# con68k-switch.net
KiCad netlist of a schematic drawn in EAGLE
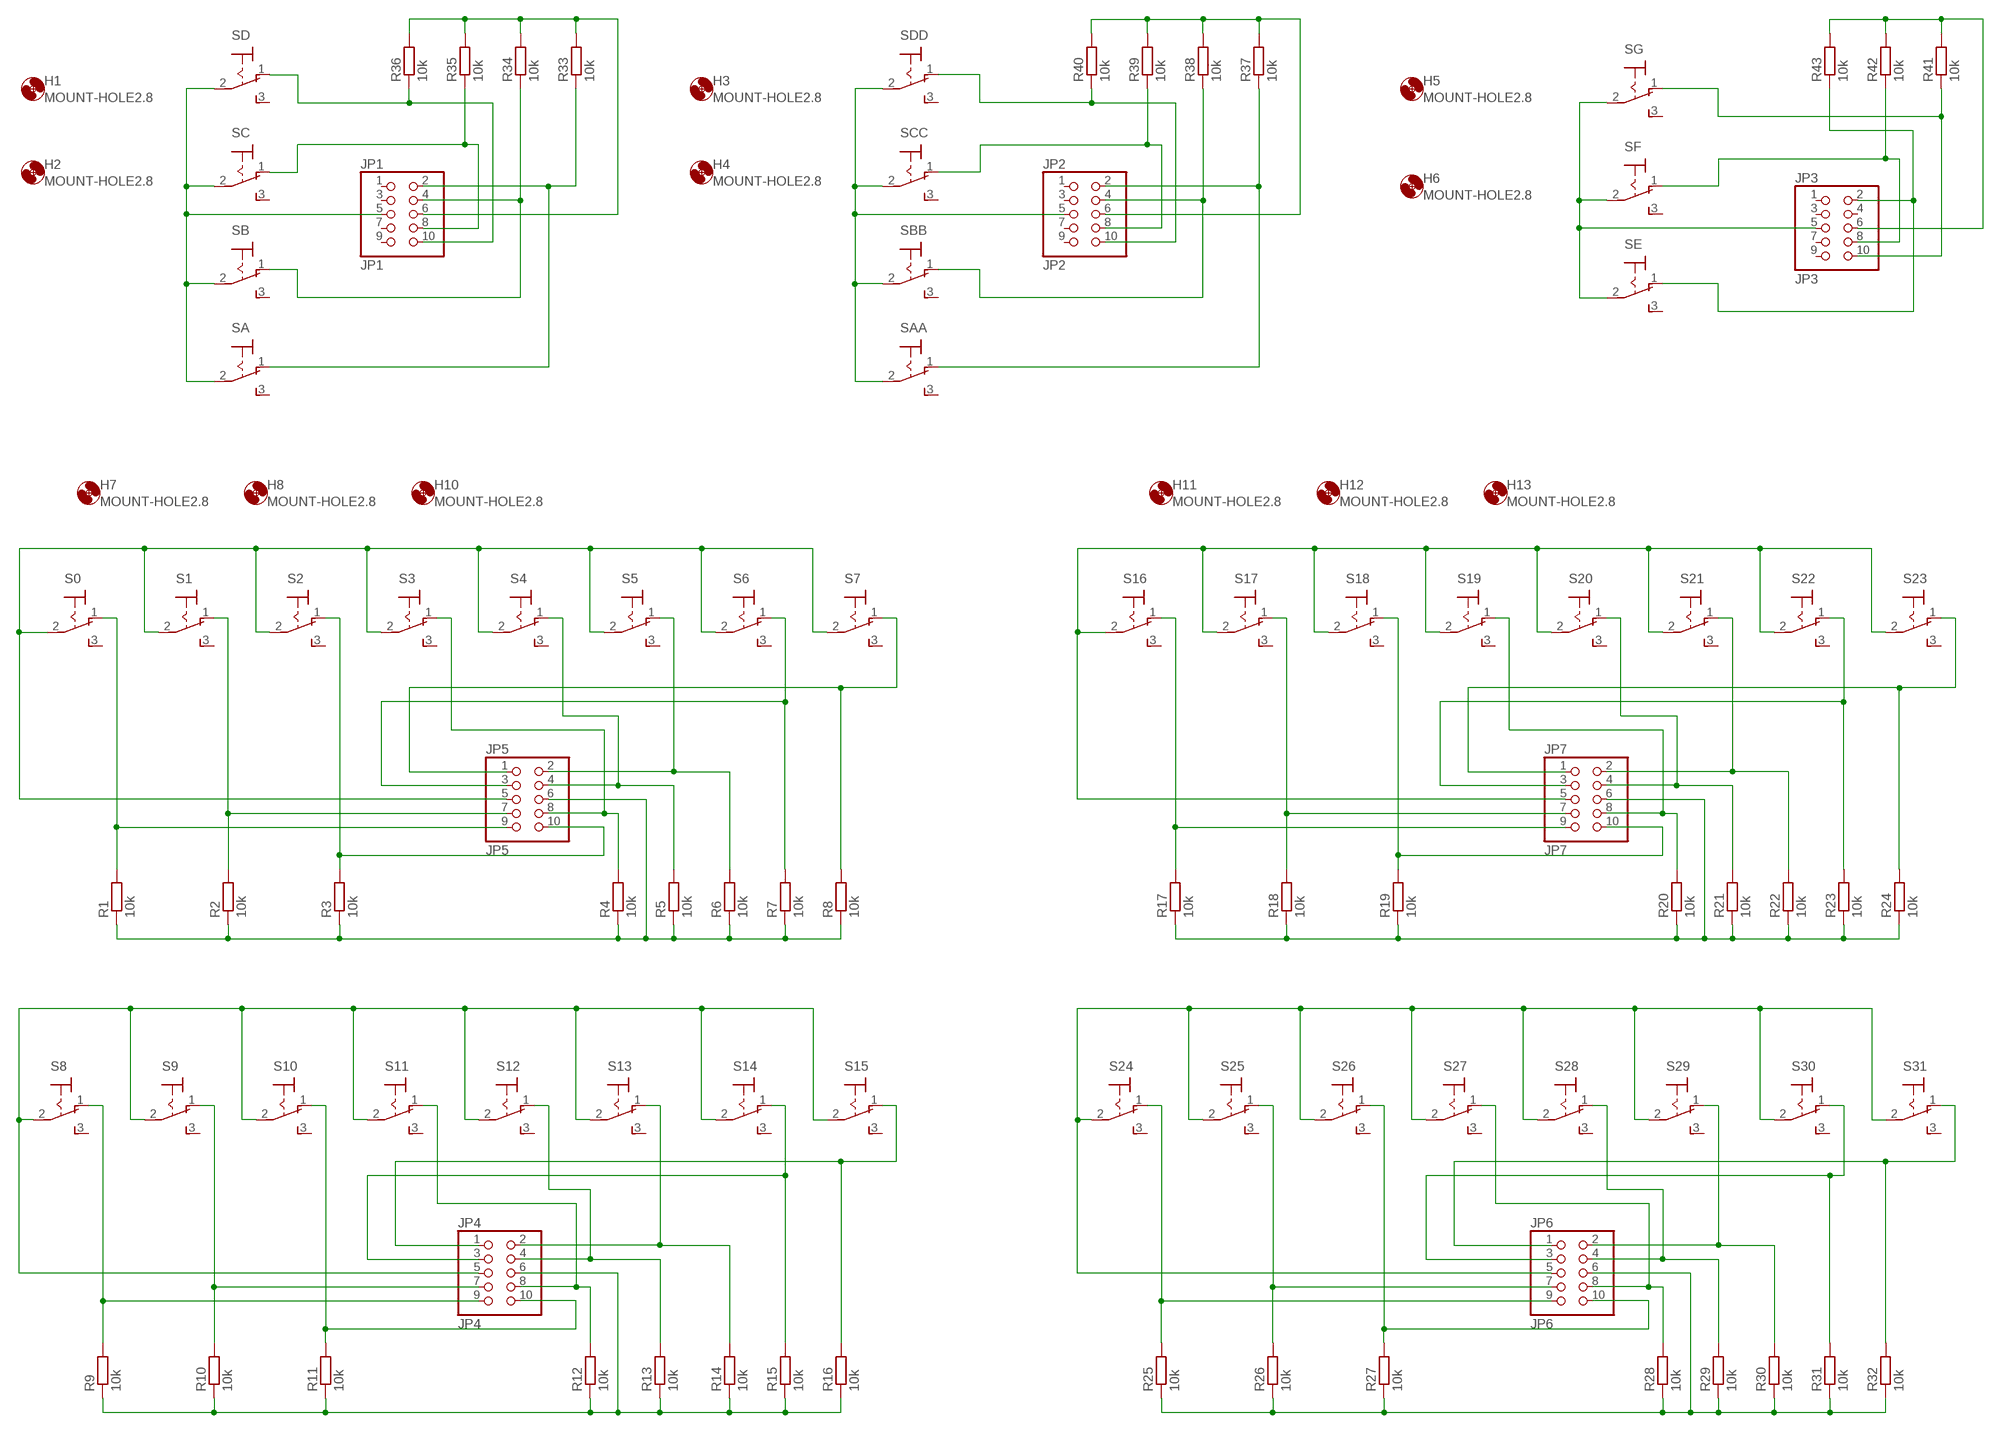
[diagram p0: schematic, sheet 1]

(export (version "E")
  (design (tool "Eeschema 10.0.6"))
  (components
    (comp (ref "H1")
      (value "MOUNT-HOLE2.8")
      (footprint "eagle-import:2,8")
      (libsource (lib "eagle-import") (part "MOUNT-HOLE2.8"))
    )
    (comp (ref "H2")
      (value "MOUNT-HOLE2.8")
      (footprint "eagle-import:2,8")
      (libsource (lib "eagle-import") (part "MOUNT-HOLE2.8"))
    )
    (comp (ref "H3")
      (value "MOUNT-HOLE2.8")
      (footprint "eagle-import:2,8")
      (libsource (lib "eagle-import") (part "MOUNT-HOLE2.8"))
    )
    (comp (ref "H4")
      (value "MOUNT-HOLE2.8")
      (footprint "eagle-import:2,8")
      (libsource (lib "eagle-import") (part "MOUNT-HOLE2.8"))
    )
    (comp (ref "H5")
      (value "MOUNT-HOLE2.8")
      (footprint "eagle-import:2,8")
      (libsource (lib "eagle-import") (part "MOUNT-HOLE2.8"))
    )
    (comp (ref "H6")
      (value "MOUNT-HOLE2.8")
      (footprint "eagle-import:2,8")
      (libsource (lib "eagle-import") (part "MOUNT-HOLE2.8"))
    )
    (comp (ref "H7")
      (value "MOUNT-HOLE2.8")
      (footprint "eagle-import:2,8")
      (libsource (lib "eagle-import") (part "MOUNT-HOLE2.8"))
    )
    (comp (ref "H8")
      (value "MOUNT-HOLE2.8")
      (footprint "eagle-import:2,8")
      (libsource (lib "eagle-import") (part "MOUNT-HOLE2.8"))
    )
    (comp (ref "H10")
      (value "MOUNT-HOLE2.8")
      (footprint "eagle-import:2,8")
      (libsource (lib "eagle-import") (part "MOUNT-HOLE2.8"))
    )
    (comp (ref "H11")
      (value "MOUNT-HOLE2.8")
      (footprint "eagle-import:2,8")
      (libsource (lib "eagle-import") (part "MOUNT-HOLE2.8"))
    )
    (comp (ref "H12")
      (value "MOUNT-HOLE2.8")
      (footprint "eagle-import:2,8")
      (libsource (lib "eagle-import") (part "MOUNT-HOLE2.8"))
    )
    (comp (ref "H13")
      (value "MOUNT-HOLE2.8")
      (footprint "eagle-import:2,8")
      (libsource (lib "eagle-import") (part "MOUNT-HOLE2.8"))
    )
    (comp (ref "JP1")
      (value "JP1")
      (footprint "eagle-import:2X05")
      (libsource (lib "eagle-import") (part "PINHD-2X5"))
    )
    (comp (ref "JP2")
      (value "JP2")
      (footprint "eagle-import:2X05")
      (libsource (lib "eagle-import") (part "PINHD-2X5"))
    )
    (comp (ref "JP3")
      (value "JP3")
      (footprint "eagle-import:2X05")
      (libsource (lib "eagle-import") (part "PINHD-2X5"))
    )
    (comp (ref "JP4")
      (value "JP4")
      (footprint "eagle-import:2X05")
      (libsource (lib "eagle-import") (part "PINHD-2X5"))
    )
    (comp (ref "JP5")
      (value "JP5")
      (footprint "eagle-import:2X05")
      (libsource (lib "eagle-import") (part "PINHD-2X5"))
    )
    (comp (ref "JP6")
      (value "JP6")
      (footprint "eagle-import:2X05")
      (libsource (lib "eagle-import") (part "PINHD-2X5"))
    )
    (comp (ref "JP7")
      (value "JP7")
      (footprint "eagle-import:2X05")
      (libsource (lib "eagle-import") (part "PINHD-2X5"))
    )
    (comp (ref "R1")
      (value "10k")
      (footprint "eagle-import:0204_7")
      (libsource (lib "eagle-import") (part "R-EU_0204/7"))
    )
    (comp (ref "R2")
      (value "10k")
      (footprint "eagle-import:0204_7")
      (libsource (lib "eagle-import") (part "R-EU_0204/7"))
    )
    (comp (ref "R3")
      (value "10k")
      (footprint "eagle-import:0204_7")
      (libsource (lib "eagle-import") (part "R-EU_0204/7"))
    )
    (comp (ref "R4")
      (value "10k")
      (footprint "eagle-import:0204_7")
      (libsource (lib "eagle-import") (part "R-EU_0204/7"))
    )
    (comp (ref "R5")
      (value "10k")
      (footprint "eagle-import:0204_7")
      (libsource (lib "eagle-import") (part "R-EU_0204/7"))
    )
    (comp (ref "R6")
      (value "10k")
      (footprint "eagle-import:0204_7")
      (libsource (lib "eagle-import") (part "R-EU_0204/7"))
    )
    (comp (ref "R7")
      (value "10k")
      (footprint "eagle-import:0204_7")
      (libsource (lib "eagle-import") (part "R-EU_0204/7"))
    )
    (comp (ref "R8")
      (value "10k")
      (footprint "eagle-import:0204_7")
      (libsource (lib "eagle-import") (part "R-EU_0204/7"))
    )
    (comp (ref "R9")
      (value "10k")
      (footprint "eagle-import:0204_7")
      (libsource (lib "eagle-import") (part "R-EU_0204/7"))
    )
    (comp (ref "R10")
      (value "10k")
      (footprint "eagle-import:0204_7")
      (libsource (lib "eagle-import") (part "R-EU_0204/7"))
    )
    (comp (ref "R11")
      (value "10k")
      (footprint "eagle-import:0204_7")
      (libsource (lib "eagle-import") (part "R-EU_0204/7"))
    )
    (comp (ref "R12")
      (value "10k")
      (footprint "eagle-import:0204_7")
      (libsource (lib "eagle-import") (part "R-EU_0204/7"))
    )
    (comp (ref "R13")
      (value "10k")
      (footprint "eagle-import:0204_7")
      (libsource (lib "eagle-import") (part "R-EU_0204/7"))
    )
    (comp (ref "R14")
      (value "10k")
      (footprint "eagle-import:0204_7")
      (libsource (lib "eagle-import") (part "R-EU_0204/7"))
    )
    (comp (ref "R15")
      (value "10k")
      (footprint "eagle-import:0204_7")
      (libsource (lib "eagle-import") (part "R-EU_0204/7"))
    )
    (comp (ref "R16")
      (value "10k")
      (footprint "eagle-import:0204_7")
      (libsource (lib "eagle-import") (part "R-EU_0204/7"))
    )
    (comp (ref "R17")
      (value "10k")
      (footprint "eagle-import:0204_7")
      (libsource (lib "eagle-import") (part "R-EU_0204/7"))
    )
    (comp (ref "R18")
      (value "10k")
      (footprint "eagle-import:0204_7")
      (libsource (lib "eagle-import") (part "R-EU_0204/7"))
    )
    (comp (ref "R19")
      (value "10k")
      (footprint "eagle-import:0204_7")
      (libsource (lib "eagle-import") (part "R-EU_0204/7"))
    )
    (comp (ref "R20")
      (value "10k")
      (footprint "eagle-import:0204_7")
      (libsource (lib "eagle-import") (part "R-EU_0204/7"))
    )
    (comp (ref "R21")
      (value "10k")
      (footprint "eagle-import:0204_7")
      (libsource (lib "eagle-import") (part "R-EU_0204/7"))
    )
    (comp (ref "R22")
      (value "10k")
      (footprint "eagle-import:0204_7")
      (libsource (lib "eagle-import") (part "R-EU_0204/7"))
    )
    (comp (ref "R23")
      (value "10k")
      (footprint "eagle-import:0204_7")
      (libsource (lib "eagle-import") (part "R-EU_0204/7"))
    )
    (comp (ref "R24")
      (value "10k")
      (footprint "eagle-import:0204_7")
      (libsource (lib "eagle-import") (part "R-EU_0204/7"))
    )
    (comp (ref "R25")
      (value "10k")
      (footprint "eagle-import:0204_7")
      (libsource (lib "eagle-import") (part "R-EU_0204/7"))
    )
    (comp (ref "R26")
      (value "10k")
      (footprint "eagle-import:0204_7")
      (libsource (lib "eagle-import") (part "R-EU_0204/7"))
    )
    (comp (ref "R27")
      (value "10k")
      (footprint "eagle-import:0204_7")
      (libsource (lib "eagle-import") (part "R-EU_0204/7"))
    )
    (comp (ref "R28")
      (value "10k")
      (footprint "eagle-import:0204_7")
      (libsource (lib "eagle-import") (part "R-EU_0204/7"))
    )
    (comp (ref "R29")
      (value "10k")
      (footprint "eagle-import:0204_7")
      (libsource (lib "eagle-import") (part "R-EU_0204/7"))
    )
    (comp (ref "R30")
      (value "10k")
      (footprint "eagle-import:0204_7")
      (libsource (lib "eagle-import") (part "R-EU_0204/7"))
    )
    (comp (ref "R31")
      (value "10k")
      (footprint "eagle-import:0204_7")
      (libsource (lib "eagle-import") (part "R-EU_0204/7"))
    )
    (comp (ref "R32")
      (value "10k")
      (footprint "eagle-import:0204_7")
      (libsource (lib "eagle-import") (part "R-EU_0204/7"))
    )
    (comp (ref "R33")
      (value "10k")
      (footprint "eagle-import:0204_7")
      (libsource (lib "eagle-import") (part "R-EU_0204/7"))
    )
    (comp (ref "R34")
      (value "10k")
      (footprint "eagle-import:0204_7")
      (libsource (lib "eagle-import") (part "R-EU_0204/7"))
    )
    (comp (ref "R35")
      (value "10k")
      (footprint "eagle-import:0204_7")
      (libsource (lib "eagle-import") (part "R-EU_0204/7"))
    )
    (comp (ref "R36")
      (value "10k")
      (footprint "eagle-import:0204_7")
      (libsource (lib "eagle-import") (part "R-EU_0204/7"))
    )
    (comp (ref "R37")
      (value "10k")
      (footprint "eagle-import:0204_7")
      (libsource (lib "eagle-import") (part "R-EU_0204/7"))
    )
    (comp (ref "R38")
      (value "10k")
      (footprint "eagle-import:0204_7")
      (libsource (lib "eagle-import") (part "R-EU_0204/7"))
    )
    (comp (ref "R39")
      (value "10k")
      (footprint "eagle-import:0204_7")
      (libsource (lib "eagle-import") (part "R-EU_0204/7"))
    )
    (comp (ref "R40")
      (value "10k")
      (footprint "eagle-import:0204_7")
      (libsource (lib "eagle-import") (part "R-EU_0204/7"))
    )
    (comp (ref "R41")
      (value "10k")
      (footprint "eagle-import:0204_7")
      (libsource (lib "eagle-import") (part "R-EU_0204/7"))
    )
    (comp (ref "R42")
      (value "10k")
      (footprint "eagle-import:0204_7")
      (libsource (lib "eagle-import") (part "R-EU_0204/7"))
    )
    (comp (ref "R43")
      (value "10k")
      (footprint "eagle-import:0204_7")
      (libsource (lib "eagle-import") (part "R-EU_0204/7"))
    )
    (comp (ref "S0")
      (value "M9040P")
      (footprint "eagle-import:M9040P")
      (libsource (lib "eagle-import") (part "M9040P"))
    )
    (comp (ref "S1")
      (value "M9040P")
      (footprint "eagle-import:M9040P")
      (libsource (lib "eagle-import") (part "M9040P"))
    )
    (comp (ref "S2")
      (value "M9040P")
      (footprint "eagle-import:M9040P")
      (libsource (lib "eagle-import") (part "M9040P"))
    )
    (comp (ref "S3")
      (value "M9040P")
      (footprint "eagle-import:M9040P")
      (libsource (lib "eagle-import") (part "M9040P"))
    )
    (comp (ref "S4")
      (value "M9040P")
      (footprint "eagle-import:M9040P")
      (libsource (lib "eagle-import") (part "M9040P"))
    )
    (comp (ref "S5")
      (value "M9040P")
      (footprint "eagle-import:M9040P")
      (libsource (lib "eagle-import") (part "M9040P"))
    )
    (comp (ref "S6")
      (value "M9040P")
      (footprint "eagle-import:M9040P")
      (libsource (lib "eagle-import") (part "M9040P"))
    )
    (comp (ref "S7")
      (value "M9040P")
      (footprint "eagle-import:M9040P")
      (libsource (lib "eagle-import") (part "M9040P"))
    )
    (comp (ref "S8")
      (value "M9040P")
      (footprint "eagle-import:M9040P")
      (libsource (lib "eagle-import") (part "M9040P"))
    )
    (comp (ref "S9")
      (value "M9040P")
      (footprint "eagle-import:M9040P")
      (libsource (lib "eagle-import") (part "M9040P"))
    )
    (comp (ref "S10")
      (value "M9040P")
      (footprint "eagle-import:M9040P")
      (libsource (lib "eagle-import") (part "M9040P"))
    )
    (comp (ref "S11")
      (value "M9040P")
      (footprint "eagle-import:M9040P")
      (libsource (lib "eagle-import") (part "M9040P"))
    )
    (comp (ref "S12")
      (value "M9040P")
      (footprint "eagle-import:M9040P")
      (libsource (lib "eagle-import") (part "M9040P"))
    )
    (comp (ref "S13")
      (value "M9040P")
      (footprint "eagle-import:M9040P")
      (libsource (lib "eagle-import") (part "M9040P"))
    )
    (comp (ref "S14")
      (value "M9040P")
      (footprint "eagle-import:M9040P")
      (libsource (lib "eagle-import") (part "M9040P"))
    )
    (comp (ref "S15")
      (value "M9040P")
      (footprint "eagle-import:M9040P")
      (libsource (lib "eagle-import") (part "M9040P"))
    )
    (comp (ref "S16")
      (value "M9040P")
      (footprint "eagle-import:M9040P")
      (libsource (lib "eagle-import") (part "M9040P"))
    )
    (comp (ref "S17")
      (value "M9040P")
      (footprint "eagle-import:M9040P")
      (libsource (lib "eagle-import") (part "M9040P"))
    )
    (comp (ref "S18")
      (value "M9040P")
      (footprint "eagle-import:M9040P")
      (libsource (lib "eagle-import") (part "M9040P"))
    )
    (comp (ref "S19")
      (value "M9040P")
      (footprint "eagle-import:M9040P")
      (libsource (lib "eagle-import") (part "M9040P"))
    )
    (comp (ref "S20")
      (value "M9040P")
      (footprint "eagle-import:M9040P")
      (libsource (lib "eagle-import") (part "M9040P"))
    )
    (comp (ref "S21")
      (value "M9040P")
      (footprint "eagle-import:M9040P")
      (libsource (lib "eagle-import") (part "M9040P"))
    )
    (comp (ref "S22")
      (value "M9040P")
      (footprint "eagle-import:M9040P")
      (libsource (lib "eagle-import") (part "M9040P"))
    )
    (comp (ref "S23")
      (value "M9040P")
      (footprint "eagle-import:M9040P")
      (libsource (lib "eagle-import") (part "M9040P"))
    )
    (comp (ref "S24")
      (value "M9040P")
      (footprint "eagle-import:M9040P")
      (libsource (lib "eagle-import") (part "M9040P"))
    )
    (comp (ref "S25")
      (value "M9040P")
      (footprint "eagle-import:M9040P")
      (libsource (lib "eagle-import") (part "M9040P"))
    )
    (comp (ref "S26")
      (value "M9040P")
      (footprint "eagle-import:M9040P")
      (libsource (lib "eagle-import") (part "M9040P"))
    )
    (comp (ref "S27")
      (value "M9040P")
      (footprint "eagle-import:M9040P")
      (libsource (lib "eagle-import") (part "M9040P"))
    )
    (comp (ref "S28")
      (value "M9040P")
      (footprint "eagle-import:M9040P")
      (libsource (lib "eagle-import") (part "M9040P"))
    )
    (comp (ref "S29")
      (value "M9040P")
      (footprint "eagle-import:M9040P")
      (libsource (lib "eagle-import") (part "M9040P"))
    )
    (comp (ref "S30")
      (value "M9040P")
      (footprint "eagle-import:M9040P")
      (libsource (lib "eagle-import") (part "M9040P"))
    )
    (comp (ref "S31")
      (value "M9040P")
      (footprint "eagle-import:M9040P")
      (libsource (lib "eagle-import") (part "M9040P"))
    )
    (comp (ref "SA")
      (value "M9040P")
      (footprint "eagle-import:M9040P")
      (libsource (lib "eagle-import") (part "M9040P"))
    )
    (comp (ref "SAA")
      (value "M9040P")
      (footprint "eagle-import:M9040P")
      (libsource (lib "eagle-import") (part "M9040P"))
    )
    (comp (ref "SB")
      (value "M9040P")
      (footprint "eagle-import:M9040P")
      (libsource (lib "eagle-import") (part "M9040P"))
    )
    (comp (ref "SBB")
      (value "M9040P")
      (footprint "eagle-import:M9040P")
      (libsource (lib "eagle-import") (part "M9040P"))
    )
    (comp (ref "SC")
      (value "M9040P")
      (footprint "eagle-import:M9040P")
      (libsource (lib "eagle-import") (part "M9040P"))
    )
    (comp (ref "SCC")
      (value "M9040P")
      (footprint "eagle-import:M9040P")
      (libsource (lib "eagle-import") (part "M9040P"))
    )
    (comp (ref "SD")
      (value "M9040P")
      (footprint "eagle-import:M9040P")
      (libsource (lib "eagle-import") (part "M9040P"))
    )
    (comp (ref "SDD")
      (value "M9040P")
      (footprint "eagle-import:M9040P")
      (libsource (lib "eagle-import") (part "M9040P"))
    )
    (comp (ref "SE")
      (value "M9040P")
      (footprint "eagle-import:M9040P")
      (libsource (lib "eagle-import") (part "M9040P"))
    )
    (comp (ref "SF")
      (value "M9040P")
      (footprint "eagle-import:M9040P")
      (libsource (lib "eagle-import") (part "M9040P"))
    )
    (comp (ref "SG")
      (value "M9040P")
      (footprint "eagle-import:M9040P")
      (libsource (lib "eagle-import") (part "M9040P"))
    )
  )
  (nets
    (net (code "1") (name "Net-(JP1-Pad6)") (class "Default")
      (node (ref "JP1") (pin "6") (pinfunction "6_6") (pintype "passive"))
      (node (ref "R33") (pin "2") (pinfunction "2_2") (pintype "passive"))
      (node (ref "R34") (pin "2") (pinfunction "2_2") (pintype "passive"))
      (node (ref "R35") (pin "2") (pinfunction "2_2") (pintype "passive"))
      (node (ref "R36") (pin "2") (pinfunction "2_2") (pintype "passive"))
    )
    (net (code "2") (name "Net-(JP2-Pad6)") (class "Default")
      (node (ref "JP2") (pin "6") (pinfunction "6_6") (pintype "passive"))
      (node (ref "R37") (pin "2") (pinfunction "2_2") (pintype "passive"))
      (node (ref "R38") (pin "2") (pinfunction "2_2") (pintype "passive"))
      (node (ref "R39") (pin "2") (pinfunction "2_2") (pintype "passive"))
      (node (ref "R40") (pin "2") (pinfunction "2_2") (pintype "passive"))
    )
    (net (code "3") (name "Net-(JP3-Pad6)") (class "Default")
      (node (ref "JP3") (pin "6") (pinfunction "6_6") (pintype "passive"))
      (node (ref "R41") (pin "2") (pinfunction "2_2") (pintype "passive"))
      (node (ref "R42") (pin "2") (pinfunction "2_2") (pintype "passive"))
      (node (ref "R43") (pin "2") (pinfunction "2_2") (pintype "passive"))
    )
    (net (code "4") (name "Net-(JP4-Pad6)") (class "Default")
      (node (ref "JP4") (pin "6") (pinfunction "6_6") (pintype "passive"))
      (node (ref "R10") (pin "1") (pinfunction "1_1") (pintype "passive"))
      (node (ref "R11") (pin "1") (pinfunction "1_1") (pintype "passive"))
      (node (ref "R12") (pin "1") (pinfunction "1_1") (pintype "passive"))
      (node (ref "R13") (pin "1") (pinfunction "1_1") (pintype "passive"))
      (node (ref "R14") (pin "1") (pinfunction "1_1") (pintype "passive"))
      (node (ref "R15") (pin "1") (pinfunction "1_1") (pintype "passive"))
      (node (ref "R16") (pin "1") (pinfunction "1_1") (pintype "passive"))
      (node (ref "R9") (pin "1") (pinfunction "1_1") (pintype "passive"))
    )
    (net (code "5") (name "Net-(JP5-Pad6)") (class "Default")
      (node (ref "JP5") (pin "6") (pinfunction "6_6") (pintype "passive"))
      (node (ref "R1") (pin "1") (pinfunction "1_1") (pintype "passive"))
      (node (ref "R2") (pin "1") (pinfunction "1_1") (pintype "passive"))
      (node (ref "R3") (pin "1") (pinfunction "1_1") (pintype "passive"))
      (node (ref "R4") (pin "1") (pinfunction "1_1") (pintype "passive"))
      (node (ref "R5") (pin "1") (pinfunction "1_1") (pintype "passive"))
      (node (ref "R6") (pin "1") (pinfunction "1_1") (pintype "passive"))
      (node (ref "R7") (pin "1") (pinfunction "1_1") (pintype "passive"))
      (node (ref "R8") (pin "1") (pinfunction "1_1") (pintype "passive"))
    )
    (net (code "6") (name "Net-(JP6-Pad6)") (class "Default")
      (node (ref "JP6") (pin "6") (pinfunction "6_6") (pintype "passive"))
      (node (ref "R25") (pin "1") (pinfunction "1_1") (pintype "passive"))
      (node (ref "R26") (pin "1") (pinfunction "1_1") (pintype "passive"))
      (node (ref "R27") (pin "1") (pinfunction "1_1") (pintype "passive"))
      (node (ref "R28") (pin "1") (pinfunction "1_1") (pintype "passive"))
      (node (ref "R29") (pin "1") (pinfunction "1_1") (pintype "passive"))
      (node (ref "R30") (pin "1") (pinfunction "1_1") (pintype "passive"))
      (node (ref "R31") (pin "1") (pinfunction "1_1") (pintype "passive"))
      (node (ref "R32") (pin "1") (pinfunction "1_1") (pintype "passive"))
    )
    (net (code "7") (name "Net-(JP7-Pad6)") (class "Default")
      (node (ref "JP7") (pin "6") (pinfunction "6_6") (pintype "passive"))
      (node (ref "R17") (pin "1") (pinfunction "1_1") (pintype "passive"))
      (node (ref "R18") (pin "1") (pinfunction "1_1") (pintype "passive"))
      (node (ref "R19") (pin "1") (pinfunction "1_1") (pintype "passive"))
      (node (ref "R20") (pin "1") (pinfunction "1_1") (pintype "passive"))
      (node (ref "R21") (pin "1") (pinfunction "1_1") (pintype "passive"))
      (node (ref "R22") (pin "1") (pinfunction "1_1") (pintype "passive"))
      (node (ref "R23") (pin "1") (pinfunction "1_1") (pintype "passive"))
      (node (ref "R24") (pin "1") (pinfunction "1_1") (pintype "passive"))
    )
    (net (code "8") (name "Net-(S0-O)") (class "Default")
      (node (ref "JP5") (pin "9") (pinfunction "9_9") (pintype "passive"))
      (node (ref "R1") (pin "2") (pinfunction "2_2") (pintype "passive"))
      (node (ref "S0") (pin "1") (pinfunction "O_1") (pintype "passive"))
    )
    (net (code "9") (name "Net-(S0-P)") (class "Default")
      (node (ref "JP5") (pin "5") (pinfunction "5_5") (pintype "passive"))
      (node (ref "S0") (pin "2") (pinfunction "P_2") (pintype "passive"))
      (node (ref "S1") (pin "2") (pinfunction "P_2") (pintype "passive"))
      (node (ref "S2") (pin "2") (pinfunction "P_2") (pintype "passive"))
      (node (ref "S3") (pin "2") (pinfunction "P_2") (pintype "passive"))
      (node (ref "S4") (pin "2") (pinfunction "P_2") (pintype "passive"))
      (node (ref "S5") (pin "2") (pinfunction "P_2") (pintype "passive"))
      (node (ref "S6") (pin "2") (pinfunction "P_2") (pintype "passive"))
      (node (ref "S7") (pin "2") (pinfunction "P_2") (pintype "passive"))
    )
    (net (code "10") (name "Net-(S1-O)") (class "Default")
      (node (ref "JP5") (pin "7") (pinfunction "7_7") (pintype "passive"))
      (node (ref "R2") (pin "2") (pinfunction "2_2") (pintype "passive"))
      (node (ref "S1") (pin "1") (pinfunction "O_1") (pintype "passive"))
    )
    (net (code "11") (name "Net-(S2-O)") (class "Default")
      (node (ref "JP5") (pin "10") (pinfunction "10_10") (pintype "passive"))
      (node (ref "R3") (pin "2") (pinfunction "2_2") (pintype "passive"))
      (node (ref "S2") (pin "1") (pinfunction "O_1") (pintype "passive"))
    )
    (net (code "12") (name "Net-(S3-O)") (class "Default")
      (node (ref "JP5") (pin "8") (pinfunction "8_8") (pintype "passive"))
      (node (ref "R4") (pin "2") (pinfunction "2_2") (pintype "passive"))
      (node (ref "S3") (pin "1") (pinfunction "O_1") (pintype "passive"))
    )
    (net (code "13") (name "Net-(S4-O)") (class "Default")
      (node (ref "JP5") (pin "4") (pinfunction "4_4") (pintype "passive"))
      (node (ref "R5") (pin "2") (pinfunction "2_2") (pintype "passive"))
      (node (ref "S4") (pin "1") (pinfunction "O_1") (pintype "passive"))
    )
    (net (code "14") (name "Net-(S5-O)") (class "Default")
      (node (ref "JP5") (pin "2") (pinfunction "2_2") (pintype "passive"))
      (node (ref "R6") (pin "2") (pinfunction "2_2") (pintype "passive"))
      (node (ref "S5") (pin "1") (pinfunction "O_1") (pintype "passive"))
    )
    (net (code "15") (name "Net-(S6-O)") (class "Default")
      (node (ref "JP5") (pin "3") (pinfunction "3_3") (pintype "passive"))
      (node (ref "R7") (pin "2") (pinfunction "2_2") (pintype "passive"))
      (node (ref "S6") (pin "1") (pinfunction "O_1") (pintype "passive"))
    )
    (net (code "16") (name "Net-(S7-O)") (class "Default")
      (node (ref "JP5") (pin "1") (pinfunction "1_1") (pintype "passive"))
      (node (ref "R8") (pin "2") (pinfunction "2_2") (pintype "passive"))
      (node (ref "S7") (pin "1") (pinfunction "O_1") (pintype "passive"))
    )
    (net (code "17") (name "Net-(S8-O)") (class "Default")
      (node (ref "JP4") (pin "9") (pinfunction "9_9") (pintype "passive"))
      (node (ref "R9") (pin "2") (pinfunction "2_2") (pintype "passive"))
      (node (ref "S8") (pin "1") (pinfunction "O_1") (pintype "passive"))
    )
    (net (code "18") (name "Net-(S9-O)") (class "Default")
      (node (ref "JP4") (pin "7") (pinfunction "7_7") (pintype "passive"))
      (node (ref "R10") (pin "2") (pinfunction "2_2") (pintype "passive"))
      (node (ref "S9") (pin "1") (pinfunction "O_1") (pintype "passive"))
    )
    (net (code "19") (name "Net-(S10-O)") (class "Default")
      (node (ref "JP4") (pin "10") (pinfunction "10_10") (pintype "passive"))
      (node (ref "R11") (pin "2") (pinfunction "2_2") (pintype "passive"))
      (node (ref "S10") (pin "1") (pinfunction "O_1") (pintype "passive"))
    )
    (net (code "20") (name "Net-(S10-P)") (class "Default")
      (node (ref "JP4") (pin "5") (pinfunction "5_5") (pintype "passive"))
      (node (ref "S10") (pin "2") (pinfunction "P_2") (pintype "passive"))
      (node (ref "S11") (pin "2") (pinfunction "P_2") (pintype "passive"))
      (node (ref "S12") (pin "2") (pinfunction "P_2") (pintype "passive"))
      (node (ref "S13") (pin "2") (pinfunction "P_2") (pintype "passive"))
      (node (ref "S14") (pin "2") (pinfunction "P_2") (pintype "passive"))
      (node (ref "S15") (pin "2") (pinfunction "P_2") (pintype "passive"))
      (node (ref "S8") (pin "2") (pinfunction "P_2") (pintype "passive"))
      (node (ref "S9") (pin "2") (pinfunction "P_2") (pintype "passive"))
    )
    (net (code "21") (name "Net-(S11-O)") (class "Default")
      (node (ref "JP4") (pin "8") (pinfunction "8_8") (pintype "passive"))
      (node (ref "R12") (pin "2") (pinfunction "2_2") (pintype "passive"))
      (node (ref "S11") (pin "1") (pinfunction "O_1") (pintype "passive"))
    )
    (net (code "22") (name "Net-(S12-O)") (class "Default")
      (node (ref "JP4") (pin "4") (pinfunction "4_4") (pintype "passive"))
      (node (ref "R13") (pin "2") (pinfunction "2_2") (pintype "passive"))
      (node (ref "S12") (pin "1") (pinfunction "O_1") (pintype "passive"))
    )
    (net (code "23") (name "Net-(S13-O)") (class "Default")
      (node (ref "JP4") (pin "2") (pinfunction "2_2") (pintype "passive"))
      (node (ref "R14") (pin "2") (pinfunction "2_2") (pintype "passive"))
      (node (ref "S13") (pin "1") (pinfunction "O_1") (pintype "passive"))
    )
    (net (code "24") (name "Net-(S14-O)") (class "Default")
      (node (ref "JP4") (pin "3") (pinfunction "3_3") (pintype "passive"))
      (node (ref "R15") (pin "2") (pinfunction "2_2") (pintype "passive"))
      (node (ref "S14") (pin "1") (pinfunction "O_1") (pintype "passive"))
    )
    (net (code "25") (name "Net-(S15-O)") (class "Default")
      (node (ref "JP4") (pin "1") (pinfunction "1_1") (pintype "passive"))
      (node (ref "R16") (pin "2") (pinfunction "2_2") (pintype "passive"))
      (node (ref "S15") (pin "1") (pinfunction "O_1") (pintype "passive"))
    )
    (net (code "26") (name "Net-(S16-O)") (class "Default")
      (node (ref "JP7") (pin "9") (pinfunction "9_9") (pintype "passive"))
      (node (ref "R17") (pin "2") (pinfunction "2_2") (pintype "passive"))
      (node (ref "S16") (pin "1") (pinfunction "O_1") (pintype "passive"))
    )
    (net (code "27") (name "Net-(S16-P)") (class "Default")
      (node (ref "JP7") (pin "5") (pinfunction "5_5") (pintype "passive"))
      (node (ref "S16") (pin "2") (pinfunction "P_2") (pintype "passive"))
      (node (ref "S17") (pin "2") (pinfunction "P_2") (pintype "passive"))
      (node (ref "S18") (pin "2") (pinfunction "P_2") (pintype "passive"))
      (node (ref "S19") (pin "2") (pinfunction "P_2") (pintype "passive"))
      (node (ref "S20") (pin "2") (pinfunction "P_2") (pintype "passive"))
      (node (ref "S21") (pin "2") (pinfunction "P_2") (pintype "passive"))
      (node (ref "S22") (pin "2") (pinfunction "P_2") (pintype "passive"))
      (node (ref "S23") (pin "2") (pinfunction "P_2") (pintype "passive"))
    )
    (net (code "28") (name "Net-(S17-O)") (class "Default")
      (node (ref "JP7") (pin "7") (pinfunction "7_7") (pintype "passive"))
      (node (ref "R18") (pin "2") (pinfunction "2_2") (pintype "passive"))
      (node (ref "S17") (pin "1") (pinfunction "O_1") (pintype "passive"))
    )
    (net (code "29") (name "Net-(S18-O)") (class "Default")
      (node (ref "JP7") (pin "10") (pinfunction "10_10") (pintype "passive"))
      (node (ref "R19") (pin "2") (pinfunction "2_2") (pintype "passive"))
      (node (ref "S18") (pin "1") (pinfunction "O_1") (pintype "passive"))
    )
    (net (code "30") (name "Net-(S19-O)") (class "Default")
      (node (ref "JP7") (pin "8") (pinfunction "8_8") (pintype "passive"))
      (node (ref "R20") (pin "2") (pinfunction "2_2") (pintype "passive"))
      (node (ref "S19") (pin "1") (pinfunction "O_1") (pintype "passive"))
    )
    (net (code "31") (name "Net-(S20-O)") (class "Default")
      (node (ref "JP7") (pin "4") (pinfunction "4_4") (pintype "passive"))
      (node (ref "R21") (pin "2") (pinfunction "2_2") (pintype "passive"))
      (node (ref "S20") (pin "1") (pinfunction "O_1") (pintype "passive"))
    )
    (net (code "32") (name "Net-(S21-O)") (class "Default")
      (node (ref "JP7") (pin "2") (pinfunction "2_2") (pintype "passive"))
      (node (ref "R22") (pin "2") (pinfunction "2_2") (pintype "passive"))
      (node (ref "S21") (pin "1") (pinfunction "O_1") (pintype "passive"))
    )
    (net (code "33") (name "Net-(S22-O)") (class "Default")
      (node (ref "JP7") (pin "3") (pinfunction "3_3") (pintype "passive"))
      (node (ref "R23") (pin "2") (pinfunction "2_2") (pintype "passive"))
      (node (ref "S22") (pin "1") (pinfunction "O_1") (pintype "passive"))
    )
    (net (code "34") (name "Net-(S23-O)") (class "Default")
      (node (ref "JP7") (pin "1") (pinfunction "1_1") (pintype "passive"))
      (node (ref "R24") (pin "2") (pinfunction "2_2") (pintype "passive"))
      (node (ref "S23") (pin "1") (pinfunction "O_1") (pintype "passive"))
    )
    (net (code "35") (name "Net-(S24-O)") (class "Default")
      (node (ref "JP6") (pin "9") (pinfunction "9_9") (pintype "passive"))
      (node (ref "R25") (pin "2") (pinfunction "2_2") (pintype "passive"))
      (node (ref "S24") (pin "1") (pinfunction "O_1") (pintype "passive"))
    )
    (net (code "36") (name "Net-(S24-P)") (class "Default")
      (node (ref "JP6") (pin "5") (pinfunction "5_5") (pintype "passive"))
      (node (ref "S24") (pin "2") (pinfunction "P_2") (pintype "passive"))
      (node (ref "S25") (pin "2") (pinfunction "P_2") (pintype "passive"))
      (node (ref "S26") (pin "2") (pinfunction "P_2") (pintype "passive"))
      (node (ref "S27") (pin "2") (pinfunction "P_2") (pintype "passive"))
      (node (ref "S28") (pin "2") (pinfunction "P_2") (pintype "passive"))
      (node (ref "S29") (pin "2") (pinfunction "P_2") (pintype "passive"))
      (node (ref "S30") (pin "2") (pinfunction "P_2") (pintype "passive"))
      (node (ref "S31") (pin "2") (pinfunction "P_2") (pintype "passive"))
    )
    (net (code "37") (name "Net-(S25-O)") (class "Default")
      (node (ref "JP6") (pin "7") (pinfunction "7_7") (pintype "passive"))
      (node (ref "R26") (pin "2") (pinfunction "2_2") (pintype "passive"))
      (node (ref "S25") (pin "1") (pinfunction "O_1") (pintype "passive"))
    )
    (net (code "38") (name "Net-(S26-O)") (class "Default")
      (node (ref "JP6") (pin "10") (pinfunction "10_10") (pintype "passive"))
      (node (ref "R27") (pin "2") (pinfunction "2_2") (pintype "passive"))
      (node (ref "S26") (pin "1") (pinfunction "O_1") (pintype "passive"))
    )
    (net (code "39") (name "Net-(S27-O)") (class "Default")
      (node (ref "JP6") (pin "8") (pinfunction "8_8") (pintype "passive"))
      (node (ref "R28") (pin "2") (pinfunction "2_2") (pintype "passive"))
      (node (ref "S27") (pin "1") (pinfunction "O_1") (pintype "passive"))
    )
    (net (code "40") (name "Net-(S28-O)") (class "Default")
      (node (ref "JP6") (pin "4") (pinfunction "4_4") (pintype "passive"))
      (node (ref "R29") (pin "2") (pinfunction "2_2") (pintype "passive"))
      (node (ref "S28") (pin "1") (pinfunction "O_1") (pintype "passive"))
    )
    (net (code "41") (name "Net-(S29-O)") (class "Default")
      (node (ref "JP6") (pin "2") (pinfunction "2_2") (pintype "passive"))
      (node (ref "R30") (pin "2") (pinfunction "2_2") (pintype "passive"))
      (node (ref "S29") (pin "1") (pinfunction "O_1") (pintype "passive"))
    )
    (net (code "42") (name "Net-(S30-O)") (class "Default")
      (node (ref "JP6") (pin "3") (pinfunction "3_3") (pintype "passive"))
      (node (ref "R31") (pin "2") (pinfunction "2_2") (pintype "passive"))
      (node (ref "S30") (pin "1") (pinfunction "O_1") (pintype "passive"))
    )
    (net (code "43") (name "Net-(S31-O)") (class "Default")
      (node (ref "JP6") (pin "1") (pinfunction "1_1") (pintype "passive"))
      (node (ref "R32") (pin "2") (pinfunction "2_2") (pintype "passive"))
      (node (ref "S31") (pin "1") (pinfunction "O_1") (pintype "passive"))
    )
    (net (code "44") (name "Net-(SA-O)") (class "Default")
      (node (ref "JP1") (pin "2") (pinfunction "2_2") (pintype "passive"))
      (node (ref "R33") (pin "1") (pinfunction "1_1") (pintype "passive"))
      (node (ref "SA") (pin "1") (pinfunction "O_1") (pintype "passive"))
    )
    (net (code "45") (name "Net-(SA-P)") (class "Default")
      (node (ref "JP1") (pin "5") (pinfunction "5_5") (pintype "passive"))
      (node (ref "SA") (pin "2") (pinfunction "P_2") (pintype "passive"))
      (node (ref "SB") (pin "2") (pinfunction "P_2") (pintype "passive"))
      (node (ref "SC") (pin "2") (pinfunction "P_2") (pintype "passive"))
      (node (ref "SD") (pin "2") (pinfunction "P_2") (pintype "passive"))
    )
    (net (code "46") (name "Net-(SAA-O)") (class "Default")
      (node (ref "JP2") (pin "2") (pinfunction "2_2") (pintype "passive"))
      (node (ref "R37") (pin "1") (pinfunction "1_1") (pintype "passive"))
      (node (ref "SAA") (pin "1") (pinfunction "O_1") (pintype "passive"))
    )
    (net (code "47") (name "Net-(SAA-P)") (class "Default")
      (node (ref "JP2") (pin "5") (pinfunction "5_5") (pintype "passive"))
      (node (ref "SAA") (pin "2") (pinfunction "P_2") (pintype "passive"))
      (node (ref "SBB") (pin "2") (pinfunction "P_2") (pintype "passive"))
      (node (ref "SCC") (pin "2") (pinfunction "P_2") (pintype "passive"))
      (node (ref "SDD") (pin "2") (pinfunction "P_2") (pintype "passive"))
    )
    (net (code "48") (name "Net-(SB-O)") (class "Default")
      (node (ref "JP1") (pin "4") (pinfunction "4_4") (pintype "passive"))
      (node (ref "R34") (pin "1") (pinfunction "1_1") (pintype "passive"))
      (node (ref "SB") (pin "1") (pinfunction "O_1") (pintype "passive"))
    )
    (net (code "49") (name "Net-(SBB-O)") (class "Default")
      (node (ref "JP2") (pin "4") (pinfunction "4_4") (pintype "passive"))
      (node (ref "R38") (pin "1") (pinfunction "1_1") (pintype "passive"))
      (node (ref "SBB") (pin "1") (pinfunction "O_1") (pintype "passive"))
    )
    (net (code "50") (name "Net-(SC-O)") (class "Default")
      (node (ref "JP1") (pin "8") (pinfunction "8_8") (pintype "passive"))
      (node (ref "R35") (pin "1") (pinfunction "1_1") (pintype "passive"))
      (node (ref "SC") (pin "1") (pinfunction "O_1") (pintype "passive"))
    )
    (net (code "51") (name "Net-(SCC-O)") (class "Default")
      (node (ref "JP2") (pin "8") (pinfunction "8_8") (pintype "passive"))
      (node (ref "R39") (pin "1") (pinfunction "1_1") (pintype "passive"))
      (node (ref "SCC") (pin "1") (pinfunction "O_1") (pintype "passive"))
    )
    (net (code "52") (name "Net-(SD-O)") (class "Default")
      (node (ref "JP1") (pin "10") (pinfunction "10_10") (pintype "passive"))
      (node (ref "R36") (pin "1") (pinfunction "1_1") (pintype "passive"))
      (node (ref "SD") (pin "1") (pinfunction "O_1") (pintype "passive"))
    )
    (net (code "53") (name "Net-(SDD-O)") (class "Default")
      (node (ref "JP2") (pin "10") (pinfunction "10_10") (pintype "passive"))
      (node (ref "R40") (pin "1") (pinfunction "1_1") (pintype "passive"))
      (node (ref "SDD") (pin "1") (pinfunction "O_1") (pintype "passive"))
    )
    (net (code "54") (name "Net-(SE-O)") (class "Default")
      (node (ref "JP3") (pin "2") (pinfunction "2_2") (pintype "passive"))
      (node (ref "R43") (pin "1") (pinfunction "1_1") (pintype "passive"))
      (node (ref "SE") (pin "1") (pinfunction "O_1") (pintype "passive"))
    )
    (net (code "55") (name "Net-(SE-P)") (class "Default")
      (node (ref "JP3") (pin "5") (pinfunction "5_5") (pintype "passive"))
      (node (ref "SE") (pin "2") (pinfunction "P_2") (pintype "passive"))
      (node (ref "SF") (pin "2") (pinfunction "P_2") (pintype "passive"))
      (node (ref "SG") (pin "2") (pinfunction "P_2") (pintype "passive"))
    )
    (net (code "56") (name "Net-(SF-O)") (class "Default")
      (node (ref "JP3") (pin "8") (pinfunction "8_8") (pintype "passive"))
      (node (ref "R42") (pin "1") (pinfunction "1_1") (pintype "passive"))
      (node (ref "SF") (pin "1") (pinfunction "O_1") (pintype "passive"))
    )
    (net (code "57") (name "Net-(SG-O)") (class "Default")
      (node (ref "JP3") (pin "10") (pinfunction "10_10") (pintype "passive"))
      (node (ref "R41") (pin "1") (pinfunction "1_1") (pintype "passive"))
      (node (ref "SG") (pin "1") (pinfunction "O_1") (pintype "passive"))
    )
    (net (code "58") (name "unconnected-(JP1-Pad1)") (class "Default")
      (node (ref "JP1") (pin "1") (pinfunction "1_1") (pintype "passive"))
    )
    (net (code "59") (name "unconnected-(JP1-Pad3)") (class "Default")
      (node (ref "JP1") (pin "3") (pinfunction "3_3") (pintype "passive"))
    )
    (net (code "60") (name "unconnected-(JP1-Pad7)") (class "Default")
      (node (ref "JP1") (pin "7") (pinfunction "7_7") (pintype "passive"))
    )
    (net (code "61") (name "unconnected-(JP1-Pad9)") (class "Default")
      (node (ref "JP1") (pin "9") (pinfunction "9_9") (pintype "passive"))
    )
    (net (code "62") (name "unconnected-(JP2-Pad1)") (class "Default")
      (node (ref "JP2") (pin "1") (pinfunction "1_1") (pintype "passive"))
    )
    (net (code "63") (name "unconnected-(JP2-Pad3)") (class "Default")
      (node (ref "JP2") (pin "3") (pinfunction "3_3") (pintype "passive"))
    )
    (net (code "64") (name "unconnected-(JP2-Pad7)") (class "Default")
      (node (ref "JP2") (pin "7") (pinfunction "7_7") (pintype "passive"))
    )
    (net (code "65") (name "unconnected-(JP2-Pad9)") (class "Default")
      (node (ref "JP2") (pin "9") (pinfunction "9_9") (pintype "passive"))
    )
    (net (code "66") (name "unconnected-(JP3-Pad1)") (class "Default")
      (node (ref "JP3") (pin "1") (pinfunction "1_1") (pintype "passive"))
    )
    (net (code "67") (name "unconnected-(JP3-Pad3)") (class "Default")
      (node (ref "JP3") (pin "3") (pinfunction "3_3") (pintype "passive"))
    )
    (net (code "68") (name "unconnected-(JP3-Pad4)") (class "Default")
      (node (ref "JP3") (pin "4") (pinfunction "4_4") (pintype "passive"))
    )
    (net (code "69") (name "unconnected-(JP3-Pad7)") (class "Default")
      (node (ref "JP3") (pin "7") (pinfunction "7_7") (pintype "passive"))
    )
    (net (code "70") (name "unconnected-(JP3-Pad9)") (class "Default")
      (node (ref "JP3") (pin "9") (pinfunction "9_9") (pintype "passive"))
    )
    (net (code "71") (name "unconnected-(S0-S-Pad3)") (class "Default")
      (node (ref "S0") (pin "3") (pinfunction "S_3") (pintype "passive"))
    )
    (net (code "72") (name "unconnected-(S1-S-Pad3)") (class "Default")
      (node (ref "S1") (pin "3") (pinfunction "S_3") (pintype "passive"))
    )
    (net (code "73") (name "unconnected-(S2-S-Pad3)") (class "Default")
      (node (ref "S2") (pin "3") (pinfunction "S_3") (pintype "passive"))
    )
    (net (code "74") (name "unconnected-(S3-S-Pad3)") (class "Default")
      (node (ref "S3") (pin "3") (pinfunction "S_3") (pintype "passive"))
    )
    (net (code "75") (name "unconnected-(S4-S-Pad3)") (class "Default")
      (node (ref "S4") (pin "3") (pinfunction "S_3") (pintype "passive"))
    )
    (net (code "76") (name "unconnected-(S5-S-Pad3)") (class "Default")
      (node (ref "S5") (pin "3") (pinfunction "S_3") (pintype "passive"))
    )
    (net (code "77") (name "unconnected-(S6-S-Pad3)") (class "Default")
      (node (ref "S6") (pin "3") (pinfunction "S_3") (pintype "passive"))
    )
    (net (code "78") (name "unconnected-(S7-S-Pad3)") (class "Default")
      (node (ref "S7") (pin "3") (pinfunction "S_3") (pintype "passive"))
    )
    (net (code "79") (name "unconnected-(S8-S-Pad3)") (class "Default")
      (node (ref "S8") (pin "3") (pinfunction "S_3") (pintype "passive"))
    )
    (net (code "80") (name "unconnected-(S9-S-Pad3)") (class "Default")
      (node (ref "S9") (pin "3") (pinfunction "S_3") (pintype "passive"))
    )
    (net (code "81") (name "unconnected-(S10-S-Pad3)") (class "Default")
      (node (ref "S10") (pin "3") (pinfunction "S_3") (pintype "passive"))
    )
    (net (code "82") (name "unconnected-(S11-S-Pad3)") (class "Default")
      (node (ref "S11") (pin "3") (pinfunction "S_3") (pintype "passive"))
    )
    (net (code "83") (name "unconnected-(S12-S-Pad3)") (class "Default")
      (node (ref "S12") (pin "3") (pinfunction "S_3") (pintype "passive"))
    )
    (net (code "84") (name "unconnected-(S13-S-Pad3)") (class "Default")
      (node (ref "S13") (pin "3") (pinfunction "S_3") (pintype "passive"))
    )
    (net (code "85") (name "unconnected-(S14-S-Pad3)") (class "Default")
      (node (ref "S14") (pin "3") (pinfunction "S_3") (pintype "passive"))
    )
    (net (code "86") (name "unconnected-(S15-S-Pad3)") (class "Default")
      (node (ref "S15") (pin "3") (pinfunction "S_3") (pintype "passive"))
    )
    (net (code "87") (name "unconnected-(S16-S-Pad3)") (class "Default")
      (node (ref "S16") (pin "3") (pinfunction "S_3") (pintype "passive"))
    )
    (net (code "88") (name "unconnected-(S17-S-Pad3)") (class "Default")
      (node (ref "S17") (pin "3") (pinfunction "S_3") (pintype "passive"))
    )
    (net (code "89") (name "unconnected-(S18-S-Pad3)") (class "Default")
      (node (ref "S18") (pin "3") (pinfunction "S_3") (pintype "passive"))
    )
    (net (code "90") (name "unconnected-(S19-S-Pad3)") (class "Default")
      (node (ref "S19") (pin "3") (pinfunction "S_3") (pintype "passive"))
    )
    (net (code "91") (name "unconnected-(S20-S-Pad3)") (class "Default")
      (node (ref "S20") (pin "3") (pinfunction "S_3") (pintype "passive"))
    )
    (net (code "92") (name "unconnected-(S21-S-Pad3)") (class "Default")
      (node (ref "S21") (pin "3") (pinfunction "S_3") (pintype "passive"))
    )
    (net (code "93") (name "unconnected-(S22-S-Pad3)") (class "Default")
      (node (ref "S22") (pin "3") (pinfunction "S_3") (pintype "passive"))
    )
    (net (code "94") (name "unconnected-(S23-S-Pad3)") (class "Default")
      (node (ref "S23") (pin "3") (pinfunction "S_3") (pintype "passive"))
    )
    (net (code "95") (name "unconnected-(S24-S-Pad3)") (class "Default")
      (node (ref "S24") (pin "3") (pinfunction "S_3") (pintype "passive"))
    )
    (net (code "96") (name "unconnected-(S25-S-Pad3)") (class "Default")
      (node (ref "S25") (pin "3") (pinfunction "S_3") (pintype "passive"))
    )
    (net (code "97") (name "unconnected-(S26-S-Pad3)") (class "Default")
      (node (ref "S26") (pin "3") (pinfunction "S_3") (pintype "passive"))
    )
    (net (code "98") (name "unconnected-(S27-S-Pad3)") (class "Default")
      (node (ref "S27") (pin "3") (pinfunction "S_3") (pintype "passive"))
    )
    (net (code "99") (name "unconnected-(S28-S-Pad3)") (class "Default")
      (node (ref "S28") (pin "3") (pinfunction "S_3") (pintype "passive"))
    )
    (net (code "100") (name "unconnected-(S29-S-Pad3)") (class "Default")
      (node (ref "S29") (pin "3") (pinfunction "S_3") (pintype "passive"))
    )
    (net (code "101") (name "unconnected-(S30-S-Pad3)") (class "Default")
      (node (ref "S30") (pin "3") (pinfunction "S_3") (pintype "passive"))
    )
    (net (code "102") (name "unconnected-(S31-S-Pad3)") (class "Default")
      (node (ref "S31") (pin "3") (pinfunction "S_3") (pintype "passive"))
    )
    (net (code "103") (name "unconnected-(SA-S-Pad3)") (class "Default")
      (node (ref "SA") (pin "3") (pinfunction "S_3") (pintype "passive"))
    )
    (net (code "104") (name "unconnected-(SAA-S-Pad3)") (class "Default")
      (node (ref "SAA") (pin "3") (pinfunction "S_3") (pintype "passive"))
    )
    (net (code "105") (name "unconnected-(SB-S-Pad3)") (class "Default")
      (node (ref "SB") (pin "3") (pinfunction "S_3") (pintype "passive"))
    )
    (net (code "106") (name "unconnected-(SBB-S-Pad3)") (class "Default")
      (node (ref "SBB") (pin "3") (pinfunction "S_3") (pintype "passive"))
    )
    (net (code "107") (name "unconnected-(SC-S-Pad3)") (class "Default")
      (node (ref "SC") (pin "3") (pinfunction "S_3") (pintype "passive"))
    )
    (net (code "108") (name "unconnected-(SCC-S-Pad3)") (class "Default")
      (node (ref "SCC") (pin "3") (pinfunction "S_3") (pintype "passive"))
    )
    (net (code "109") (name "unconnected-(SD-S-Pad3)") (class "Default")
      (node (ref "SD") (pin "3") (pinfunction "S_3") (pintype "passive"))
    )
    (net (code "110") (name "unconnected-(SDD-S-Pad3)") (class "Default")
      (node (ref "SDD") (pin "3") (pinfunction "S_3") (pintype "passive"))
    )
    (net (code "111") (name "unconnected-(SE-S-Pad3)") (class "Default")
      (node (ref "SE") (pin "3") (pinfunction "S_3") (pintype "passive"))
    )
    (net (code "112") (name "unconnected-(SF-S-Pad3)") (class "Default")
      (node (ref "SF") (pin "3") (pinfunction "S_3") (pintype "passive"))
    )
    (net (code "113") (name "unconnected-(SG-S-Pad3)") (class "Default")
      (node (ref "SG") (pin "3") (pinfunction "S_3") (pintype "passive"))
    )
  )
)
